# autowater-a.net
KiCad netlist of a schematic drawn in EAGLE
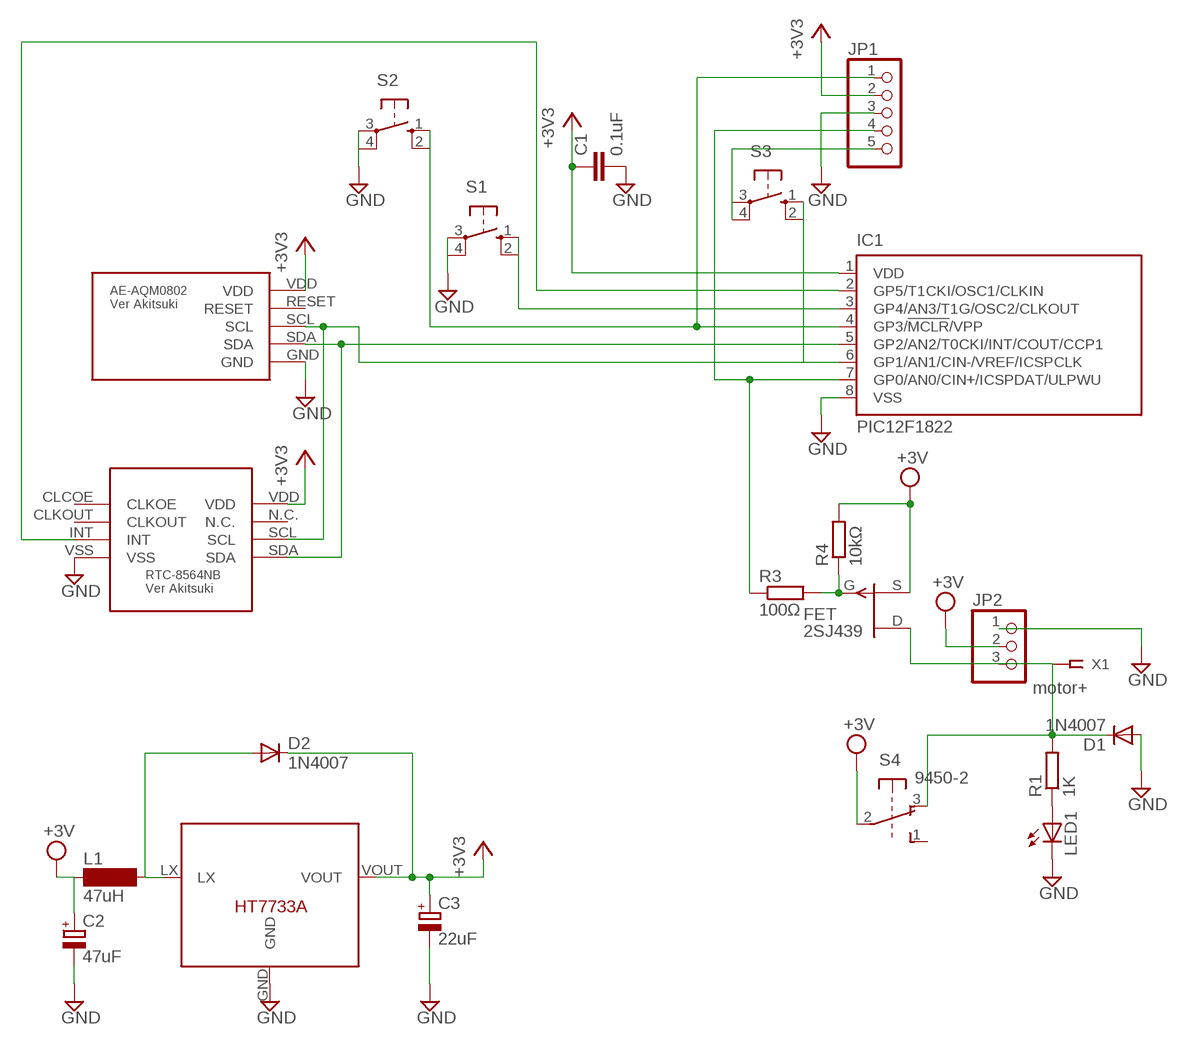
[diagram p0: schematic, sheet 1]

(export (version "E")
  (design (tool "Eeschema 10.0.6"))
  (components
    (comp (ref "C1")
      (value "0.1uF")
      (footprint "eagle-import:C7.5B3")
      (libsource (lib "eagle-import") (part "C7.5/3"))
    )
    (comp (ref "C2")
      (value "47uF")
      (footprint "eagle-import:TT2D5")
      (libsource (lib "eagle-import") (part "CPOL-EUTT2D5"))
    )
    (comp (ref "C3")
      (value "22uF")
      (footprint "eagle-import:TT2D5")
      (libsource (lib "eagle-import") (part "CPOL-EUTT2D5"))
    )
    (comp (ref "D1")
      (value "1N4007")
      (footprint "eagle-import:DO35-7")
      (libsource (lib "eagle-import") (part "1N4148DO35-7"))
    )
    (comp (ref "D2")
      (value "1N4007")
      (footprint "eagle-import:DO35-7")
      (libsource (lib "eagle-import") (part "1N4148DO35-7"))
    )
    (comp (ref "FET")
      (value "2SJ439")
      (footprint "eagle-import:2SJ439")
      (libsource (lib "eagle-import") (part "2SJ439"))
    )
    (comp (ref "IC1")
      (value "PIC12F1822")
      (footprint "eagle-import:DIL8")
      (fields
        (field (name "MF") "MICROCHIP")
        (field (name "MPN") "PIC12F683-I/P")
        (field (name "MPN_1") "PIC12F1822")
      )
      (libsource (lib "eagle-import") (part "PIC12F683P"))
    )
    (comp (ref "JP1")
      (value "PINHD-1X5")
      (footprint "eagle-import:1X05")
      (libsource (lib "eagle-import") (part "PINHD-1X5"))
    )
    (comp (ref "JP2")
      (value "PINHD-1X3")
      (footprint "eagle-import:1X03")
      (libsource (lib "eagle-import") (part "PINHD-1X3"))
    )
    (comp (ref "L1")
      (value "47uH")
      (footprint "eagle-import:SD75")
      (libsource (lib "eagle-import") (part "SD75"))
    )
    (comp (ref "LED1")
      (value "LEDLZR181")
      (footprint "eagle-import:LZR181")
      (libsource (lib "eagle-import") (part "LEDLZR181"))
    )
    (comp (ref "R1")
      (value "1K")
      (footprint "eagle-import:0204_7")
      (libsource (lib "eagle-import") (part "R-EU_0204/7"))
    )
    (comp (ref "R3")
      (value "100Ω")
      (footprint "eagle-import:0207_12")
      (libsource (lib "eagle-import") (part "R-EU_0207/12"))
    )
    (comp (ref "R4")
      (value "10kΩ")
      (footprint "eagle-import:0204_7")
      (libsource (lib "eagle-import") (part "R-EU_0204/7"))
    )
    (comp (ref "S1")
      (value "10-XX")
      (footprint "eagle-import:B3F-10XX")
      (fields
        (field (name "MPN") "B3F-1000")
        (field (name "MPN_1") "B3F-1000")
        (field (name "OC_FARNELL") "176432")
        (field (name "OC_NEWARK") "36M3542")
      )
      (libsource (lib "eagle-import") (part "10-XX"))
    )
    (comp (ref "S2")
      (value "10-XX")
      (footprint "eagle-import:B3F-10XX")
      (fields (field (name "MPN") "B3F-1000"))
      (libsource (lib "eagle-import") (part "10-XX"))
    )
    (comp (ref "S3")
      (value "10-XX")
      (footprint "eagle-import:B3F-10XX")
      (fields
        (field (name "MPN") "B3F-1000")
        (field (name "MPN_1") "B3F-1000")
        (field (name "OC_FARNELL") "176432")
        (field (name "OC_NEWARK") "36M3542")
      )
      (libsource (lib "eagle-import") (part "10-XX"))
    )
    (comp (ref "S4")
      (value "9450-2")
      (footprint "eagle-import:9450-2")
      (libsource (lib "eagle-import") (part "9450-2"))
    )
    (comp (ref "U$1")
      (value "RTC-8564NB-VER-AKITSUKI")
      (footprint "eagle-import:RTC-8564NB-VER-AKITSUKI")
      (libsource (lib "eagle-import") (part "RTC-8564NB-VER-AKITSUKI"))
    )
    (comp (ref "U$2")
      (value "AE-AQM0802-VER-AKITSUKI")
      (footprint "eagle-import:AE-AQM0802-VER-AKITSUKI")
      (libsource (lib "eagle-import") (part "AE-AQM0802-VER-AKITSUKI"))
    )
    (comp (ref "U$4")
      (value "HT7733A")
      (footprint "eagle-import:HT7733A")
      (libsource (lib "eagle-import") (part "HT7733A"))
    )
    (comp (ref "X1")
      (value "motor+")
      (footprint "eagle-import:SSW-101-02-S-S")
      (fields (field (name "MPN") "SSW-101-02-S-S"))
      (libsource (lib "eagle-import") (part "SSW-101-02-S-S"))
    )
  )
  (nets
    (net (code "1") (name "+3V") (class "Default")
      (node (ref "C2") (pin "+") (pinfunction "+_+") (pintype "passive"))
      (node (ref "FET") (pin "S") (pinfunction "S_S") (pintype "passive"))
      (node (ref "JP2") (pin "2") (pinfunction "2_2") (pintype "passive"))
      (node (ref "L1") (pin "1") (pinfunction "1_1") (pintype "passive"))
      (node (ref "R4") (pin "2") (pinfunction "2_2") (pintype "passive"))
      (node (ref "S4") (pin "2") (pinfunction "P_2") (pintype "passive"))
    )
    (net (code "2") (name "+3V3") (class "Default")
      (node (ref "C1") (pin "1") (pinfunction "1_1") (pintype "passive"))
      (node (ref "C3") (pin "+") (pinfunction "+_+") (pintype "passive"))
      (node (ref "D2") (pin "C") (pinfunction "C_C") (pintype "passive"))
      (node (ref "IC1") (pin "1") (pinfunction "VDD_1") (pintype "power_in"))
      (node (ref "JP1") (pin "2") (pinfunction "2_2") (pintype "passive"))
      (node (ref "U$1") (pin "VDD") (pinfunction "VDD_VDD") (pintype "bidirectional"))
      (node (ref "U$2") (pin "VDD") (pinfunction "VDD_VDD") (pintype "bidirectional"))
      (node (ref "U$4") (pin "VOUT") (pinfunction "VOUT_VOUT") (pintype "bidirectional"))
    )
    (net (code "3") (name "GND") (class "Default")
      (node (ref "C1") (pin "2") (pinfunction "2_2") (pintype "passive"))
      (node (ref "C2") (pin "-") (pinfunction "-_-") (pintype "passive"))
      (node (ref "C3") (pin "-") (pinfunction "-_-") (pintype "passive"))
      (node (ref "D1") (pin "A") (pinfunction "A_A") (pintype "passive"))
      (node (ref "IC1") (pin "8") (pinfunction "VSS_8") (pintype "power_in"))
      (node (ref "JP1") (pin "3") (pinfunction "3_3") (pintype "passive"))
      (node (ref "JP2") (pin "1") (pinfunction "1_1") (pintype "passive"))
      (node (ref "LED1") (pin "K") (pinfunction "C_K") (pintype "passive"))
      (node (ref "S1") (pin "3") (pinfunction "P_3") (pintype "passive"))
      (node (ref "S2") (pin "3") (pinfunction "P_3") (pintype "passive"))
      (node (ref "U$1") (pin "VSS") (pinfunction "VSS_VSS") (pintype "bidirectional"))
      (node (ref "U$2") (pin "GND") (pinfunction "GND_GND") (pintype "bidirectional"))
      (node (ref "U$4") (pin "GND") (pinfunction "GND_GND") (pintype "bidirectional"))
    )
    (net (code "4") (name "Net-(D2-PadA)") (class "Default")
      (node (ref "D2") (pin "A") (pinfunction "A_A") (pintype "passive"))
      (node (ref "L1") (pin "2") (pinfunction "2_2") (pintype "passive"))
      (node (ref "U$4") (pin "LX") (pinfunction "LX_LX") (pintype "bidirectional"))
    )
    (net (code "5") (name "Net-(FET-PadG)") (class "Default")
      (node (ref "FET") (pin "G") (pinfunction "G_G") (pintype "passive"))
      (node (ref "R3") (pin "2") (pinfunction "2_2") (pintype "passive"))
      (node (ref "R4") (pin "1") (pinfunction "1_1") (pintype "passive"))
    )
    (net (code "6") (name "Net-(IC1-GP0{slash}AN0{slash}CIN+{slash}ICSPDAT{slash}ULPWU)") (class "Default")
      (node (ref "IC1") (pin "7") (pinfunction "GP0/AN0/CIN+/ICSPDAT/ULPWU_7") (pintype "bidirectional"))
      (node (ref "JP1") (pin "4") (pinfunction "4_4") (pintype "passive"))
      (node (ref "R3") (pin "1") (pinfunction "1_1") (pintype "passive"))
    )
    (net (code "7") (name "Net-(IC1-GP1{slash}AN1{slash}CIN-{slash}VREF{slash}ICSPCLK)") (class "Default")
      (node (ref "IC1") (pin "6") (pinfunction "GP1/AN1/CIN-/VREF/ICSPCLK_6") (pintype "bidirectional"))
      (node (ref "S3") (pin "1") (pinfunction "S_1") (pintype "passive"))
      (node (ref "U$1") (pin "SCL") (pinfunction "SCL_SCL") (pintype "bidirectional"))
      (node (ref "U$2") (pin "SCL") (pinfunction "SCL_SCL") (pintype "bidirectional"))
    )
    (net (code "8") (name "Net-(IC1-GP2{slash}AN2{slash}T0CKI{slash}INT{slash}COUT{slash}CCP1)") (class "Default")
      (node (ref "IC1") (pin "5") (pinfunction "GP2/AN2/T0CKI/INT/COUT/CCP1_5") (pintype "bidirectional"))
      (node (ref "U$1") (pin "SDA") (pinfunction "SDA_SDA") (pintype "bidirectional"))
      (node (ref "U$2") (pin "SDA") (pinfunction "SDA_SDA") (pintype "bidirectional"))
    )
    (net (code "9") (name "Net-(IC1-GP3{slash}~{MCLR}{slash}VPP)") (class "Default")
      (node (ref "IC1") (pin "4") (pinfunction "GP3/~{MCLR}/VPP_4") (pintype "bidirectional"))
      (node (ref "JP1") (pin "1") (pinfunction "1_1") (pintype "passive"))
      (node (ref "S2") (pin "1") (pinfunction "S_1") (pintype "passive"))
    )
    (net (code "10") (name "Net-(IC1-GP4{slash}AN3{slash}T1G{slash}OSC2{slash}CLKOUT)") (class "Default")
      (node (ref "IC1") (pin "3") (pinfunction "GP4/AN3/T1G/OSC2/CLKOUT_3") (pintype "bidirectional"))
      (node (ref "S1") (pin "1") (pinfunction "S_1") (pintype "passive"))
    )
    (net (code "11") (name "Net-(IC1-GP5{slash}T1CKI{slash}OSC1{slash}CLKIN)") (class "Default")
      (node (ref "IC1") (pin "2") (pinfunction "GP5/T1CKI/OSC1/CLKIN_2") (pintype "bidirectional"))
      (node (ref "U$1") (pin "INT") (pinfunction "INT_INT") (pintype "bidirectional"))
    )
    (net (code "12") (name "Net-(LED1-PadA)") (class "Default")
      (node (ref "LED1") (pin "A") (pinfunction "A_A") (pintype "passive"))
      (node (ref "R1") (pin "1") (pinfunction "1_1") (pintype "passive"))
    )
    (net (code "13") (name "Net-(S3-P1)") (class "Default")
      (node (ref "JP1") (pin "5") (pinfunction "5_5") (pintype "passive"))
      (node (ref "S3") (pin "4") (pinfunction "P1_4") (pintype "passive"))
    )
    (net (code "14") (name "Net-(S4A-O)") (class "Default")
      (node (ref "D1") (pin "C") (pinfunction "C_C") (pintype "passive"))
      (node (ref "FET") (pin "D") (pinfunction "D_D") (pintype "passive"))
      (node (ref "JP2") (pin "3") (pinfunction "3_3") (pintype "passive"))
      (node (ref "R1") (pin "2") (pinfunction "2_2") (pintype "passive"))
      (node (ref "S4") (pin "3") (pinfunction "O_3") (pintype "passive"))
      (node (ref "X1") (pin "1") (pinfunction "1_1") (pintype "passive"))
    )
    (net (code "15") (name "unconnected-(S1-P1-Pad4)") (class "Default")
      (node (ref "S1") (pin "4") (pinfunction "P1_4") (pintype "passive"))
    )
    (net (code "16") (name "unconnected-(S1-S1-Pad2)") (class "Default")
      (node (ref "S1") (pin "2") (pinfunction "S1_2") (pintype "passive"))
    )
    (net (code "17") (name "unconnected-(S2-P1-Pad4)") (class "Default")
      (node (ref "S2") (pin "4") (pinfunction "P1_4") (pintype "passive"))
    )
    (net (code "18") (name "unconnected-(S2-S1-Pad2)") (class "Default")
      (node (ref "S2") (pin "2") (pinfunction "S1_2") (pintype "passive"))
    )
    (net (code "19") (name "unconnected-(S3-P-Pad3)") (class "Default")
      (node (ref "S3") (pin "3") (pinfunction "P_3") (pintype "passive"))
    )
    (net (code "20") (name "unconnected-(S3-S1-Pad2)") (class "Default")
      (node (ref "S3") (pin "2") (pinfunction "S1_2") (pintype "passive"))
    )
    (net (code "21") (name "unconnected-(S4A-S-Pad1)") (class "Default")
      (node (ref "S4") (pin "1") (pinfunction "S_1") (pintype "passive"))
    )
    (net (code "22") (name "unconnected-(U$1-CLKOE-PadCLCOE)") (class "Default")
      (node (ref "U$1") (pin "CLCOE") (pinfunction "CLKOE_CLCOE") (pintype "bidirectional"))
    )
    (net (code "23") (name "unconnected-(U$1-PadCLKOUT)") (class "Default")
      (node (ref "U$1") (pin "CLKOUT") (pinfunction "CLKOUT_CLKOUT") (pintype "bidirectional"))
    )
    (net (code "24") (name "unconnected-(U$1-PadN.C.)") (class "Default")
      (node (ref "U$1") (pin "N.C.") (pinfunction "N.C._N.C.") (pintype "bidirectional"))
    )
    (net (code "25") (name "unconnected-(U$2-PadRESET)") (class "Default")
      (node (ref "U$2") (pin "RESET") (pinfunction "RESET_RESET") (pintype "bidirectional"))
    )
  )
)
